# 1_POWER.net
KiCad netlist of a schematic drawn in Altium Designer
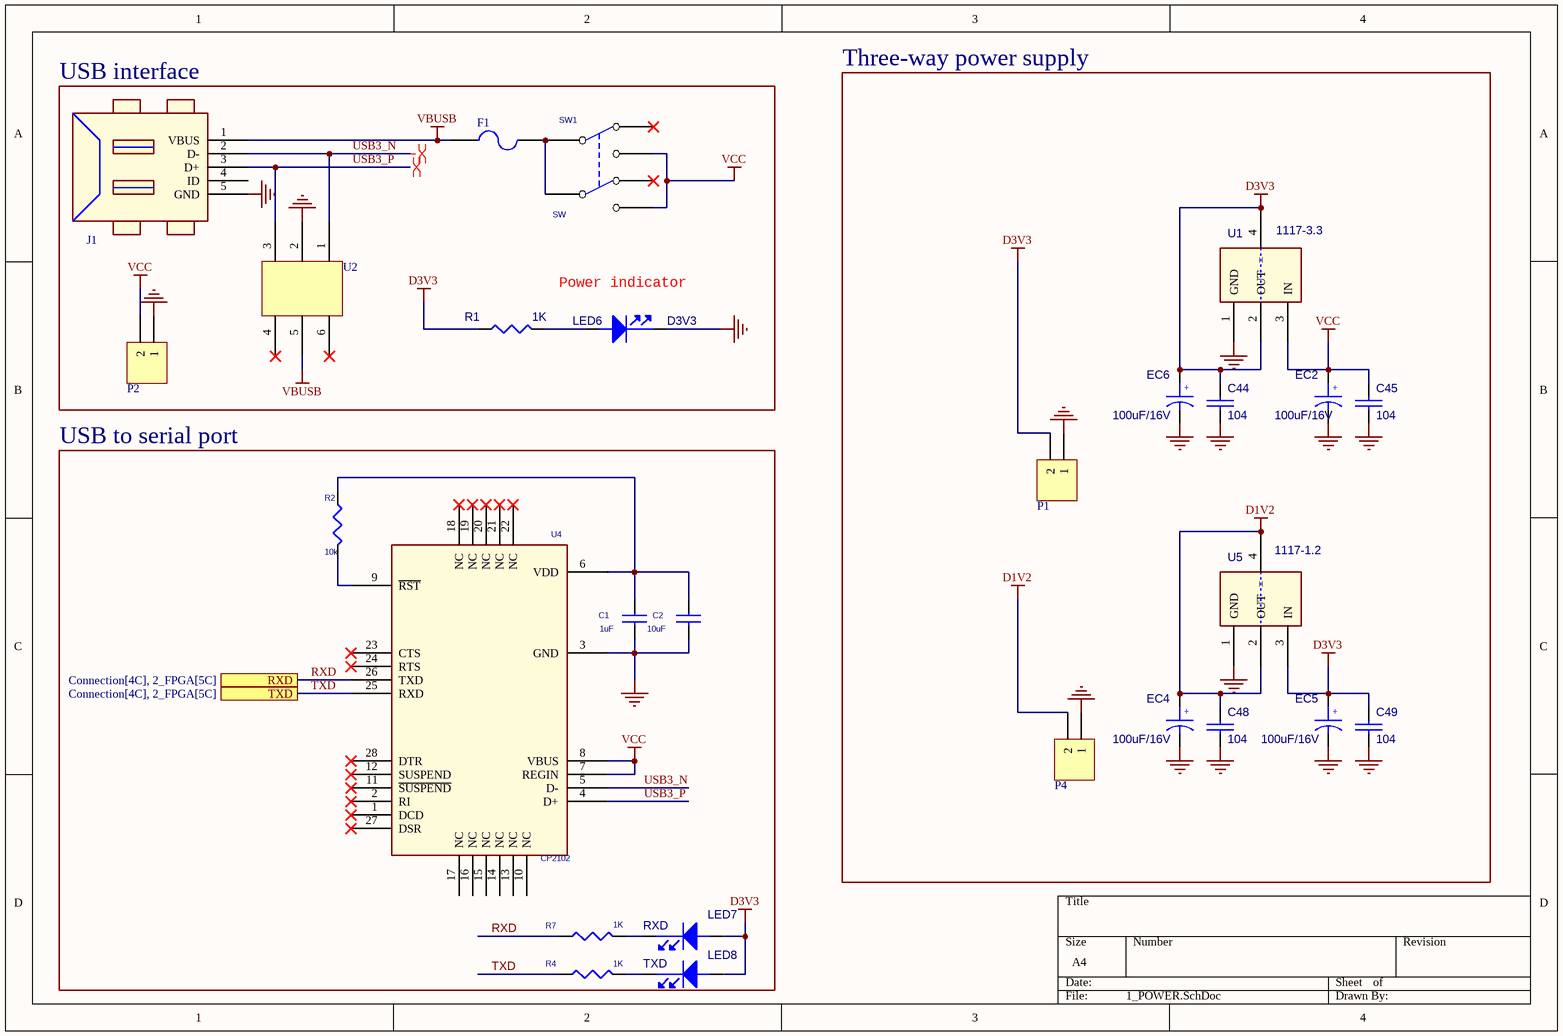
[diagram p0: 1_POWER.SchDoc]

(export (version "E")
  (design (tool "Eeschema 10.0.6"))
  (components
    (comp (ref "C1") (value "1uF") (libsource (lib "*") (part "CAP NP_Dup2")))
    (comp (ref "C2") (value "10uF") (libsource (lib "*") (part "CAP NP_Dup2")))
    (comp (ref "C44") (value "104") (libsource (lib "*") (part "C_Dup4")))
    (comp (ref "C45") (value "104") (libsource (lib "*") (part "C_Dup4")))
    (comp (ref "C48") (value "104") (libsource (lib "*") (part "C_Dup4")))
    (comp (ref "C49") (value "104") (libsource (lib "*") (part "C_Dup4")))
    (comp (ref "EC2") (value "100uF/16V") (libsource (lib "*") (part "EC")))
    (comp (ref "EC4") (value "100uF/16V") (libsource (lib "*") (part "EC")))
    (comp (ref "EC5") (value "100uF/16V") (libsource (lib "*") (part "EC")))
    (comp (ref "EC6") (value "100uF/16V") (libsource (lib "*") (part "EC")))
    (comp (ref "F1")
      (value "~")
      (footprint "1206")
      (description "Fuse")
      (fields (field (name "PUBLISHER") "Altium Limited"))
      (libsource (lib "Xilinx Spartan-6") (part "Fuse 2"))
    )
    (comp (ref "J1") (value "EC2") (footprint "MINIUSBB") (libsource (lib "*") (part "MiniUSBB")))
    (comp (ref "LED6") (value "D3V3") (footprint "LEDSO") (libsource (lib "*") (part "LED_Dup1")))
    (comp (ref "LED7") (value "RXD") (footprint "LEDSO") (libsource (lib "*") (part "LED")))
    (comp (ref "LED8") (value "TXD") (footprint "LEDSO") (libsource (lib "*") (part "LED")))
    (comp (ref "P1")
      (value "3.3V")
      (footprint "HDR1X2")
      (description "Header, 2-Pin")
      (fields (field (name "PUBLISHER") "Altium Limited"))
      (libsource (lib "Miscellaneous Connectors") (part "Header 2"))
    )
    (comp (ref "P2")
      (value "5V")
      (footprint "HDR1X2")
      (description "Header, 2-Pin")
      (fields (field (name "PUBLISHER") "Altium Limited"))
      (libsource (lib "Miscellaneous Connectors") (part "Header 2"))
    )
    (comp (ref "P4")
      (value "1.2V")
      (footprint "HDR1X2")
      (description "Header, 2-Pin")
      (fields (field (name "PUBLISHER") "Altium Limited"))
      (libsource (lib "Miscellaneous Connectors") (part "Header 2"))
    )
    (comp (ref "R1") (value "1K") (footprint "0603") (libsource (lib "*") (part "R")))
    (comp (ref "R2") (value "10k") (libsource (lib "*") (part "RESISTOR")))
    (comp (ref "R4") (value "1K") (footprint "0603") (libsource (lib "*") (part "R_Dup3")))
    (comp (ref "R7") (value "1K") (footprint "0603") (libsource (lib "*") (part "R_Dup3")))
    (comp (ref "SW1") (value "SW") (libsource (lib "*") (part "SW KEY-DPDT")))
    (comp (ref "U1") (value "1117-3.3") (footprint "SOT223") (libsource (lib "*") (part "1117-3.3")))
    (comp (ref "U2") (value "~") (footprint "SOT23-6") (libsource (lib "Xilinx Spartan-6") (part "SRV05-4")))
    (comp (ref "U4") (value "CP2102") (libsource (lib "*") (part "CP2102_0")))
    (comp (ref "U5") (value "1117-1.2") (footprint "SOT223") (libsource (lib "*") (part "1117-3.3")))
  )
  (nets
    (net (code "1") (name "/RXD") (class "Default")
      (node (ref "R7") (pin "1") (pinfunction "1_1") (pintype "passive"))
      (node (ref "U4") (pin "26") (pinfunction "TXD_26") (pintype "passive"))
    )
    (net (code "2") (name "/TXD") (class "Default")
      (node (ref "R4") (pin "1") (pinfunction "1_1") (pintype "passive"))
      (node (ref "U4") (pin "25") (pinfunction "RXD_25") (pintype "passive"))
    )
    (net (code "3") (name "/USB3_N") (class "Default")
      (node (ref "J1") (pin "2") (pinfunction "D-_2") (pintype "passive"))
      (node (ref "U2") (pin "1") (pinfunction "1_1") (pintype "passive"))
      (node (ref "U4") (pin "5") (pinfunction "D-_5") (pintype "passive"))
    )
    (net (code "4") (name "/USB3_P") (class "Default")
      (node (ref "J1") (pin "3") (pinfunction "D+_3") (pintype "passive"))
      (node (ref "U2") (pin "3") (pinfunction "3_3") (pintype "passive"))
      (node (ref "U4") (pin "4") (pinfunction "D+_4") (pintype "passive"))
    )
    (net (code "5") (name "D1V2") (class "Default")
      (node (ref "C48") (pin "1") (pinfunction "1_1") (pintype "passive"))
      (node (ref "EC4") (pin "1") (pinfunction "1_1") (pintype "passive"))
      (node (ref "P4") (pin "2") (pinfunction "2_2") (pintype "passive"))
      (node (ref "U5") (pin "2") (pinfunction "OUT_2") (pintype "passive"))
      (node (ref "U5") (pin "4") (pinfunction "=_4") (pintype "passive"))
    )
    (net (code "6") (name "D3V3") (class "Default")
      (node (ref "C44") (pin "1") (pinfunction "1_1") (pintype "passive"))
      (node (ref "C49") (pin "1") (pinfunction "1_1") (pintype "passive"))
      (node (ref "EC5") (pin "1") (pinfunction "1_1") (pintype "passive"))
      (node (ref "EC6") (pin "1") (pinfunction "1_1") (pintype "passive"))
      (node (ref "LED7") (pin "1") (pinfunction "ANODE_1") (pintype "passive"))
      (node (ref "LED8") (pin "1") (pinfunction "ANODE_1") (pintype "passive"))
      (node (ref "P1") (pin "2") (pinfunction "2_2") (pintype "passive"))
      (node (ref "R1") (pin "1") (pinfunction "1_1") (pintype "passive"))
      (node (ref "U1") (pin "2") (pinfunction "OUT_2") (pintype "passive"))
      (node (ref "U1") (pin "4") (pinfunction "=_4") (pintype "passive"))
      (node (ref "U5") (pin "3") (pinfunction "IN_3") (pintype "passive"))
    )
    (net (code "7") (name "GND") (class "Default")
      (node (ref "C1") (pin "2") (pinfunction "2_2") (pintype "passive"))
      (node (ref "C2") (pin "2") (pinfunction "2_2") (pintype "passive"))
      (node (ref "C44") (pin "2") (pinfunction "2_2") (pintype "passive"))
      (node (ref "C45") (pin "2") (pinfunction "2_2") (pintype "passive"))
      (node (ref "C48") (pin "2") (pinfunction "2_2") (pintype "passive"))
      (node (ref "C49") (pin "2") (pinfunction "2_2") (pintype "passive"))
      (node (ref "EC2") (pin "2") (pinfunction "2_2") (pintype "passive"))
      (node (ref "EC4") (pin "2") (pinfunction "2_2") (pintype "passive"))
      (node (ref "EC5") (pin "2") (pinfunction "2_2") (pintype "passive"))
      (node (ref "EC6") (pin "2") (pinfunction "2_2") (pintype "passive"))
      (node (ref "J1") (pin "5") (pinfunction "GND_5") (pintype "passive"))
      (node (ref "LED6") (pin "2") (pinfunction "CATHODE_2") (pintype "passive"))
      (node (ref "P1") (pin "1") (pinfunction "1_1") (pintype "passive"))
      (node (ref "P2") (pin "1") (pinfunction "1_1") (pintype "passive"))
      (node (ref "P4") (pin "1") (pinfunction "1_1") (pintype "passive"))
      (node (ref "U1") (pin "1") (pinfunction "GND_1") (pintype "passive"))
      (node (ref "U2") (pin "2") (pinfunction "2_2") (pintype "passive"))
      (node (ref "U4") (pin "3") (pinfunction "GND_3") (pintype "power_in"))
      (node (ref "U5") (pin "1") (pinfunction "GND_1") (pintype "passive"))
    )
    (net (code "8") (name "Net-(LED6-ANODE)") (class "Default")
      (node (ref "LED6") (pin "1") (pinfunction "ANODE_1") (pintype "passive"))
      (node (ref "R1") (pin "2") (pinfunction "2_2") (pintype "passive"))
    )
    (net (code "9") (name "Net-(LED7-CATHODE)") (class "Default")
      (node (ref "LED7") (pin "2") (pinfunction "CATHODE_2") (pintype "passive"))
      (node (ref "R7") (pin "2") (pinfunction "2_2") (pintype "passive"))
    )
    (net (code "10") (name "Net-(LED8-CATHODE)") (class "Default")
      (node (ref "LED8") (pin "2") (pinfunction "CATHODE_2") (pintype "passive"))
      (node (ref "R4") (pin "2") (pinfunction "2_2") (pintype "passive"))
    )
    (net (code "11") (name "Net-(SW1-COMMON1)") (class "Default")
      (node (ref "F1") (pin "2") (pinfunction "2_2") (pintype "passive"))
      (node (ref "SW1") (pin "2") (pinfunction "COMMON1_2") (pintype "passive"))
      (node (ref "SW1") (pin "5") (pinfunction "COMMON2_5") (pintype "passive"))
    )
    (net (code "12") (name "Net-(U4-VDD)") (class "Default")
      (node (ref "C1") (pin "1") (pinfunction "1_1") (pintype "passive"))
      (node (ref "C2") (pin "1") (pinfunction "1_1") (pintype "passive"))
      (node (ref "R2") (pin "2") (pinfunction "2_2") (pintype "passive"))
      (node (ref "U4") (pin "6") (pinfunction "VDD_6") (pintype "power_in"))
    )
    (net (code "13") (name "Net-(U4-~{RST})") (class "Default")
      (node (ref "R2") (pin "1") (pinfunction "1_1") (pintype "passive"))
      (node (ref "U4") (pin "9") (pinfunction "~{RST}_9") (pintype "passive"))
    )
    (net (code "14") (name "VBUSB") (class "Default")
      (node (ref "F1") (pin "1") (pinfunction "1_1") (pintype "passive"))
      (node (ref "J1") (pin "1") (pinfunction "VBUS_1") (pintype "passive"))
      (node (ref "U2") (pin "5") (pinfunction "5_5") (pintype "passive"))
    )
    (net (code "15") (name "VCC") (class "Default")
      (node (ref "C45") (pin "1") (pinfunction "1_1") (pintype "passive"))
      (node (ref "EC2") (pin "1") (pinfunction "1_1") (pintype "passive"))
      (node (ref "P2") (pin "2") (pinfunction "2_2") (pintype "passive"))
      (node (ref "SW1") (pin "3") (pinfunction "NO1_3") (pintype "passive"))
      (node (ref "SW1") (pin "6") (pinfunction "NO2_6") (pintype "passive"))
      (node (ref "U1") (pin "3") (pinfunction "IN_3") (pintype "passive"))
      (node (ref "U4") (pin "7") (pinfunction "REGIN_7") (pintype "passive"))
      (node (ref "U4") (pin "8") (pinfunction "VBUS_8") (pintype "passive"))
    )
    (net (code "16") (name "unconnected-(J1-ID-Pad4)") (class "Default")
      (node (ref "J1") (pin "4") (pinfunction "ID_4") (pintype "passive"))
    )
    (net (code "17") (name "unconnected-(SW1-NC1-Pad1)") (class "Default")
      (node (ref "SW1") (pin "1") (pinfunction "NC1_1") (pintype "passive+no_connect"))
    )
    (net (code "18") (name "unconnected-(SW1-NC2-Pad4)") (class "Default")
      (node (ref "SW1") (pin "4") (pinfunction "NC2_4") (pintype "passive+no_connect"))
    )
    (net (code "19") (name "unconnected-(U2-Pad4)") (class "Default")
      (node (ref "U2") (pin "4") (pinfunction "4_4") (pintype "passive+no_connect"))
    )
    (net (code "20") (name "unconnected-(U2-Pad6)") (class "Default")
      (node (ref "U2") (pin "6") (pinfunction "6_6") (pintype "passive+no_connect"))
    )
    (net (code "21") (name "unconnected-(U4-CTS-Pad23)") (class "Default")
      (node (ref "U4") (pin "23") (pinfunction "CTS_23") (pintype "passive+no_connect"))
    )
    (net (code "22") (name "unconnected-(U4-DCD-Pad1)") (class "Default")
      (node (ref "U4") (pin "1") (pinfunction "DCD_1") (pintype "passive+no_connect"))
    )
    (net (code "23") (name "unconnected-(U4-DSR-Pad27)") (class "Default")
      (node (ref "U4") (pin "27") (pinfunction "DSR_27") (pintype "passive+no_connect"))
    )
    (net (code "24") (name "unconnected-(U4-DTR-Pad28)") (class "Default")
      (node (ref "U4") (pin "28") (pinfunction "DTR_28") (pintype "passive+no_connect"))
    )
    (net (code "25") (name "unconnected-(U4-NC-Pad10)") (class "Default")
      (node (ref "U4") (pin "10") (pinfunction "NC_10") (pintype "passive"))
    )
    (net (code "26") (name "unconnected-(U4-NC-Pad13)") (class "Default")
      (node (ref "U4") (pin "13") (pinfunction "NC_13") (pintype "passive"))
    )
    (net (code "27") (name "unconnected-(U4-NC-Pad14)") (class "Default")
      (node (ref "U4") (pin "14") (pinfunction "NC_14") (pintype "passive"))
    )
    (net (code "28") (name "unconnected-(U4-NC-Pad15)") (class "Default")
      (node (ref "U4") (pin "15") (pinfunction "NC_15") (pintype "passive"))
    )
    (net (code "29") (name "unconnected-(U4-NC-Pad16)") (class "Default")
      (node (ref "U4") (pin "16") (pinfunction "NC_16") (pintype "passive"))
    )
    (net (code "30") (name "unconnected-(U4-NC-Pad17)") (class "Default")
      (node (ref "U4") (pin "17") (pinfunction "NC_17") (pintype "passive"))
    )
    (net (code "31") (name "unconnected-(U4-NC-Pad18)") (class "Default")
      (node (ref "U4") (pin "18") (pinfunction "NC_18") (pintype "passive+no_connect"))
    )
    (net (code "32") (name "unconnected-(U4-NC-Pad19)") (class "Default")
      (node (ref "U4") (pin "19") (pinfunction "NC_19") (pintype "passive+no_connect"))
    )
    (net (code "33") (name "unconnected-(U4-NC-Pad20)") (class "Default")
      (node (ref "U4") (pin "20") (pinfunction "NC_20") (pintype "passive+no_connect"))
    )
    (net (code "34") (name "unconnected-(U4-NC-Pad21)") (class "Default")
      (node (ref "U4") (pin "21") (pinfunction "NC_21") (pintype "passive+no_connect"))
    )
    (net (code "35") (name "unconnected-(U4-NC-Pad22)") (class "Default")
      (node (ref "U4") (pin "22") (pinfunction "NC_22") (pintype "passive+no_connect"))
    )
    (net (code "36") (name "unconnected-(U4-RI-Pad2)") (class "Default")
      (node (ref "U4") (pin "2") (pinfunction "RI_2") (pintype "passive+no_connect"))
    )
    (net (code "37") (name "unconnected-(U4-RTS-Pad24)") (class "Default")
      (node (ref "U4") (pin "24") (pinfunction "RTS_24") (pintype "passive+no_connect"))
    )
    (net (code "38") (name "unconnected-(U4-SUSPEND-Pad12)") (class "Default")
      (node (ref "U4") (pin "12") (pinfunction "SUSPEND_12") (pintype "passive+no_connect"))
    )
    (net (code "39") (name "unconnected-(U4-~{SUSPEND}-Pad11)") (class "Default")
      (node (ref "U4") (pin "11") (pinfunction "~{SUSPEND}_11") (pintype "passive+no_connect"))
    )
  )
)
